# DriversL293D.net
KiCad netlist of a schematic drawn in EAGLE
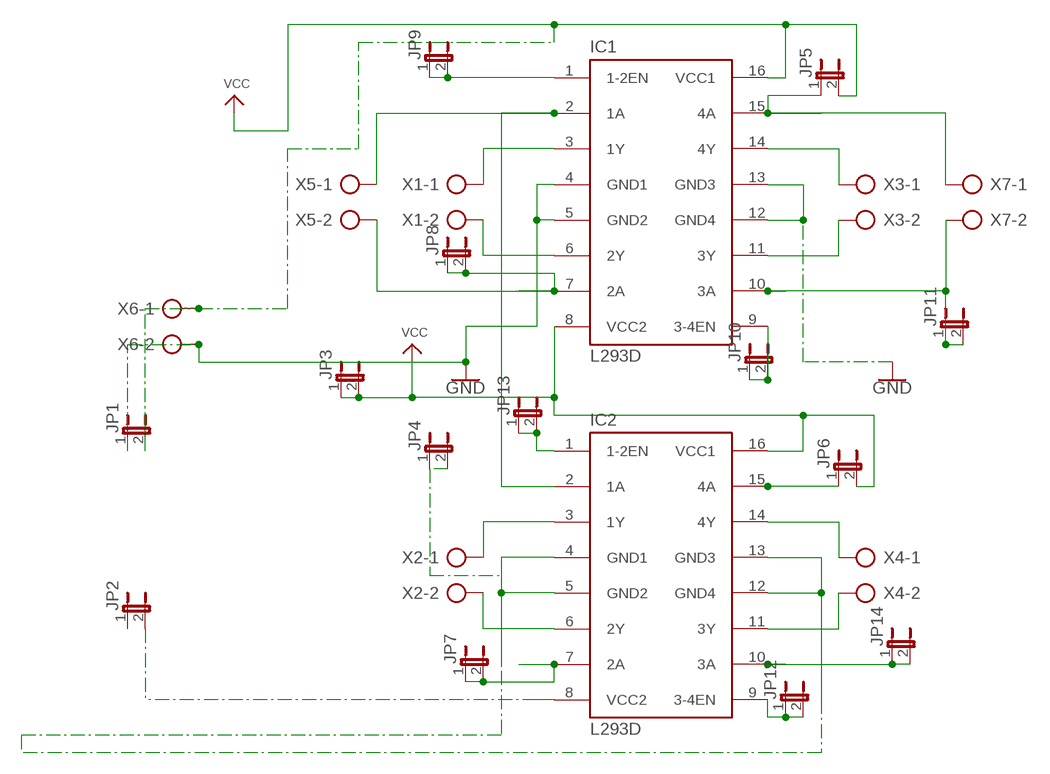
[diagram p0: schematic, sheet 1]

(export (version "E")
  (design (tool "Eeschema 10.0.6"))
  (components
    (comp (ref "IC1")
      (value "L293D")
      (footprint "eagle-import:DIL16")
      (libsource (lib "eagle-import") (part "L293D"))
    )
    (comp (ref "IC2")
      (value "L293D")
      (footprint "eagle-import:DIL16")
      (libsource (lib "eagle-import") (part "L293D"))
    )
    (comp (ref "JP1")
      (value "JP1E")
      (footprint "eagle-import:JP1")
      (libsource (lib "eagle-import") (part "JP1E"))
    )
    (comp (ref "JP2")
      (value "JP1E")
      (footprint "eagle-import:JP1")
      (libsource (lib "eagle-import") (part "JP1E"))
    )
    (comp (ref "JP3")
      (value "JP1E")
      (footprint "eagle-import:JP1")
      (libsource (lib "eagle-import") (part "JP1E"))
    )
    (comp (ref "JP4")
      (value "JP1E")
      (footprint "eagle-import:JP1")
      (libsource (lib "eagle-import") (part "JP1E"))
    )
    (comp (ref "JP5")
      (value "JP1E")
      (footprint "eagle-import:JP1")
      (libsource (lib "eagle-import") (part "JP1E"))
    )
    (comp (ref "JP6")
      (value "JP1E")
      (footprint "eagle-import:JP1")
      (libsource (lib "eagle-import") (part "JP1E"))
    )
    (comp (ref "JP7")
      (value "JP1E")
      (footprint "eagle-import:JP1")
      (libsource (lib "eagle-import") (part "JP1E"))
    )
    (comp (ref "JP8")
      (value "JP1E")
      (footprint "eagle-import:JP1")
      (libsource (lib "eagle-import") (part "JP1E"))
    )
    (comp (ref "JP9")
      (value "JP1E")
      (footprint "eagle-import:JP1")
      (libsource (lib "eagle-import") (part "JP1E"))
    )
    (comp (ref "JP10")
      (value "JP1E")
      (footprint "eagle-import:JP1")
      (libsource (lib "eagle-import") (part "JP1E"))
    )
    (comp (ref "JP11")
      (value "JP1E")
      (footprint "eagle-import:JP1")
      (libsource (lib "eagle-import") (part "JP1E"))
    )
    (comp (ref "JP12")
      (value "JP1E")
      (footprint "eagle-import:JP1")
      (libsource (lib "eagle-import") (part "JP1E"))
    )
    (comp (ref "JP13")
      (value "JP1E")
      (footprint "eagle-import:JP1")
      (libsource (lib "eagle-import") (part "JP1E"))
    )
    (comp (ref "JP14")
      (value "JP1E")
      (footprint "eagle-import:JP1")
      (libsource (lib "eagle-import") (part "JP1E"))
    )
    (comp (ref "X1")
      (value "AK500/2-H")
      (footprint "eagle-import:AK500_2-H")
      (libsource (lib "eagle-import") (part "AK500/2-H"))
    )
    (comp (ref "X2")
      (value "AK500/2-H")
      (footprint "eagle-import:AK500_2-H")
      (libsource (lib "eagle-import") (part "AK500/2-H"))
    )
    (comp (ref "X3")
      (value "AK500/2-H")
      (footprint "eagle-import:AK500_2-H")
      (libsource (lib "eagle-import") (part "AK500/2-H"))
    )
    (comp (ref "X4")
      (value "AK500/2-H")
      (footprint "eagle-import:AK500_2-H")
      (libsource (lib "eagle-import") (part "AK500/2-H"))
    )
    (comp (ref "X5")
      (value "AK500/2-H")
      (footprint "eagle-import:AK500_2-H")
      (libsource (lib "eagle-import") (part "AK500/2-H"))
    )
    (comp (ref "X6")
      (value "AK500/2-H")
      (footprint "eagle-import:AK500_2-H")
      (libsource (lib "eagle-import") (part "AK500/2-H"))
    )
    (comp (ref "X7")
      (value "AK500/2-H")
      (footprint "eagle-import:AK500_2-H")
      (libsource (lib "eagle-import") (part "AK500/2-H"))
    )
  )
  (nets
    (net (code "1") (name "GND") (class "Default")
      (node (ref "IC1") (pin "12") (pinfunction "GND4_12") (pintype "power_in"))
      (node (ref "IC1") (pin "13") (pinfunction "GND3_13") (pintype "power_in"))
      (node (ref "IC1") (pin "4") (pinfunction "GND1_4") (pintype "power_in"))
      (node (ref "IC1") (pin "5") (pinfunction "GND2_5") (pintype "power_in"))
      (node (ref "JP1") (pin "1") (pinfunction "1_1") (pintype "passive"))
      (node (ref "X6") (pin "2") (pinfunction "KL_2") (pintype "passive"))
    )
    (net (code "2") (name "Net-(IC1-1-2EN)") (class "Default")
      (node (ref "IC1") (pin "1") (pinfunction "1-2EN_1") (pintype "input"))
      (node (ref "JP9") (pin "1") (pinfunction "1_1") (pintype "passive"))
      (node (ref "JP9") (pin "2") (pinfunction "2_2") (pintype "passive"))
    )
    (net (code "3") (name "Net-(IC1-1A)") (class "Default")
      (node (ref "IC1") (pin "2") (pinfunction "1A_2") (pintype "input"))
      (node (ref "IC2") (pin "2") (pinfunction "1A_2") (pintype "input"))
      (node (ref "X5") (pin "1") (pinfunction "KL_1") (pintype "passive"))
    )
    (net (code "4") (name "Net-(IC1-1Y)") (class "Default")
      (node (ref "IC1") (pin "3") (pinfunction "1Y_3") (pintype "output"))
      (node (ref "X1") (pin "1") (pinfunction "KL_1") (pintype "passive"))
    )
    (net (code "5") (name "Net-(IC1-2A)") (class "Default")
      (node (ref "IC1") (pin "7") (pinfunction "2A_7") (pintype "input"))
      (node (ref "JP8") (pin "1") (pinfunction "1_1") (pintype "passive"))
      (node (ref "JP8") (pin "2") (pinfunction "2_2") (pintype "passive"))
      (node (ref "X5") (pin "2") (pinfunction "KL_2") (pintype "passive"))
    )
    (net (code "6") (name "Net-(IC1-2Y)") (class "Default")
      (node (ref "IC1") (pin "6") (pinfunction "2Y_6") (pintype "output"))
      (node (ref "X1") (pin "2") (pinfunction "KL_2") (pintype "passive"))
    )
    (net (code "7") (name "Net-(IC1-3-4EN)") (class "Default")
      (node (ref "IC1") (pin "9") (pinfunction "3-4EN_9") (pintype "input"))
      (node (ref "JP10") (pin "1") (pinfunction "1_1") (pintype "passive"))
      (node (ref "JP10") (pin "2") (pinfunction "2_2") (pintype "passive"))
    )
    (net (code "8") (name "Net-(IC1-3A)") (class "Default")
      (node (ref "IC1") (pin "10") (pinfunction "3A_10") (pintype "input"))
      (node (ref "JP11") (pin "1") (pinfunction "1_1") (pintype "passive"))
      (node (ref "JP11") (pin "2") (pinfunction "2_2") (pintype "passive"))
      (node (ref "X7") (pin "2") (pinfunction "KL_2") (pintype "passive"))
    )
    (net (code "9") (name "Net-(IC1-3Y)") (class "Default")
      (node (ref "IC1") (pin "11") (pinfunction "3Y_11") (pintype "output"))
      (node (ref "X3") (pin "2") (pinfunction "KL_2") (pintype "passive"))
    )
    (net (code "10") (name "Net-(IC1-4A)") (class "Default")
      (node (ref "IC1") (pin "15") (pinfunction "4A_15") (pintype "input"))
      (node (ref "JP5") (pin "1") (pinfunction "1_1") (pintype "passive"))
      (node (ref "X7") (pin "1") (pinfunction "KL_1") (pintype "passive"))
    )
    (net (code "11") (name "Net-(IC1-4Y)") (class "Default")
      (node (ref "IC1") (pin "14") (pinfunction "4Y_14") (pintype "output"))
      (node (ref "X3") (pin "1") (pinfunction "KL_1") (pintype "passive"))
    )
    (net (code "12") (name "Net-(IC2-1-2EN)") (class "Default")
      (node (ref "IC2") (pin "1") (pinfunction "1-2EN_1") (pintype "input"))
      (node (ref "JP13") (pin "1") (pinfunction "1_1") (pintype "passive"))
      (node (ref "JP13") (pin "2") (pinfunction "2_2") (pintype "passive"))
    )
    (net (code "13") (name "Net-(IC2-1Y)") (class "Default")
      (node (ref "IC2") (pin "3") (pinfunction "1Y_3") (pintype "output"))
      (node (ref "X2") (pin "1") (pinfunction "KL_1") (pintype "passive"))
    )
    (net (code "14") (name "Net-(IC2-2A)") (class "Default")
      (node (ref "IC2") (pin "7") (pinfunction "2A_7") (pintype "input"))
      (node (ref "JP7") (pin "1") (pinfunction "1_1") (pintype "passive"))
      (node (ref "JP7") (pin "2") (pinfunction "2_2") (pintype "passive"))
    )
    (net (code "15") (name "Net-(IC2-2Y)") (class "Default")
      (node (ref "IC2") (pin "6") (pinfunction "2Y_6") (pintype "output"))
      (node (ref "X2") (pin "2") (pinfunction "KL_2") (pintype "passive"))
    )
    (net (code "16") (name "Net-(IC2-3-4EN)") (class "Default")
      (node (ref "IC2") (pin "9") (pinfunction "3-4EN_9") (pintype "input"))
      (node (ref "JP12") (pin "1") (pinfunction "1_1") (pintype "passive"))
      (node (ref "JP12") (pin "2") (pinfunction "2_2") (pintype "passive"))
    )
    (net (code "17") (name "Net-(IC2-3A)") (class "Default")
      (node (ref "IC2") (pin "10") (pinfunction "3A_10") (pintype "input"))
      (node (ref "JP14") (pin "1") (pinfunction "1_1") (pintype "passive"))
      (node (ref "JP14") (pin "2") (pinfunction "2_2") (pintype "passive"))
    )
    (net (code "18") (name "Net-(IC2-3Y)") (class "Default")
      (node (ref "IC2") (pin "11") (pinfunction "3Y_11") (pintype "output"))
      (node (ref "X4") (pin "2") (pinfunction "KL_2") (pintype "passive"))
    )
    (net (code "19") (name "Net-(IC2-4A)") (class "Default")
      (node (ref "IC2") (pin "15") (pinfunction "4A_15") (pintype "input"))
      (node (ref "JP6") (pin "1") (pinfunction "1_1") (pintype "passive"))
    )
    (net (code "20") (name "Net-(IC2-4Y)") (class "Default")
      (node (ref "IC2") (pin "14") (pinfunction "4Y_14") (pintype "output"))
      (node (ref "X4") (pin "1") (pinfunction "KL_1") (pintype "passive"))
    )
    (net (code "21") (name "Net-(IC2-GND1)") (class "Default")
      (node (ref "IC2") (pin "12") (pinfunction "GND4_12") (pintype "power_in"))
      (node (ref "IC2") (pin "13") (pinfunction "GND3_13") (pintype "power_in"))
      (node (ref "IC2") (pin "4") (pinfunction "GND1_4") (pintype "power_in"))
      (node (ref "IC2") (pin "5") (pinfunction "GND2_5") (pintype "power_in"))
      (node (ref "JP4") (pin "1") (pinfunction "1_1") (pintype "passive"))
      (node (ref "JP4") (pin "2") (pinfunction "2_2") (pintype "passive"))
    )
    (net (code "22") (name "Net-(IC2-VCC2)") (class "Default")
      (node (ref "IC2") (pin "8") (pinfunction "VCC2_8") (pintype "power_in"))
      (node (ref "JP2") (pin "2") (pinfunction "2_2") (pintype "passive"))
    )
    (net (code "23") (name "VCC") (class "Default")
      (node (ref "IC1") (pin "16") (pinfunction "VCC1_16") (pintype "power_in"))
      (node (ref "IC1") (pin "8") (pinfunction "VCC2_8") (pintype "power_in"))
      (node (ref "IC2") (pin "16") (pinfunction "VCC1_16") (pintype "power_in"))
      (node (ref "JP1") (pin "2") (pinfunction "2_2") (pintype "passive"))
      (node (ref "JP3") (pin "1") (pinfunction "1_1") (pintype "passive"))
      (node (ref "JP3") (pin "2") (pinfunction "2_2") (pintype "passive"))
      (node (ref "JP5") (pin "2") (pinfunction "2_2") (pintype "passive"))
      (node (ref "JP6") (pin "2") (pinfunction "2_2") (pintype "passive"))
      (node (ref "X6") (pin "1") (pinfunction "KL_1") (pintype "passive"))
    )
    (net (code "24") (name "unconnected-(JP2-Pad1)") (class "Default")
      (node (ref "JP2") (pin "1") (pinfunction "1_1") (pintype "passive"))
    )
  )
)
